# SCH_3S_10A_BMS_2022-07-15.net
KiCad netlist of a schematic drawn in EasyEDA
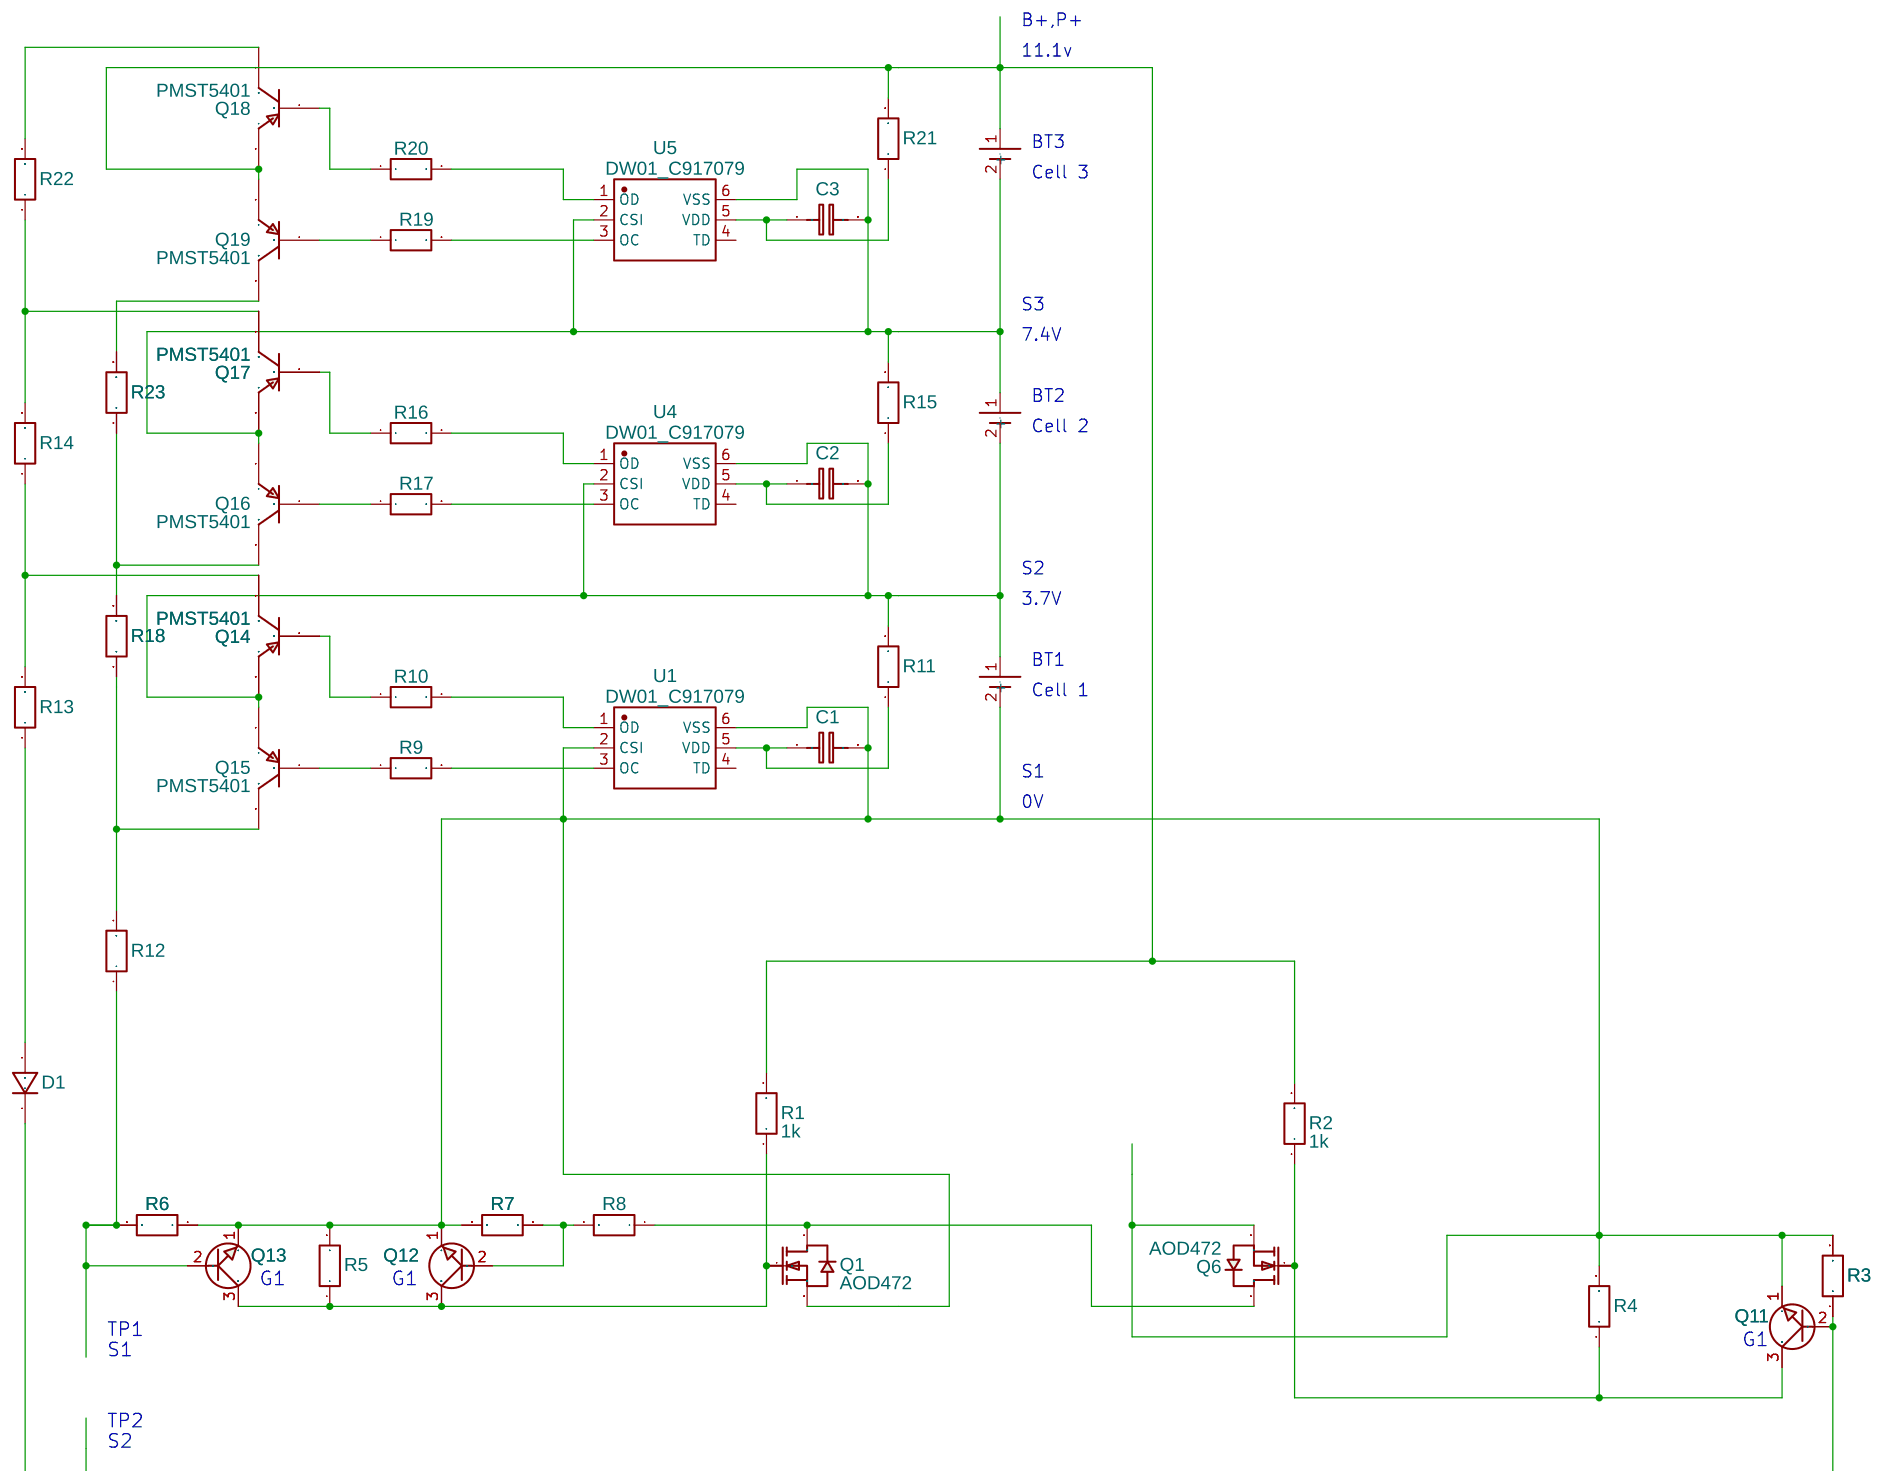
[diagram p0: 3s 10A Schematic]
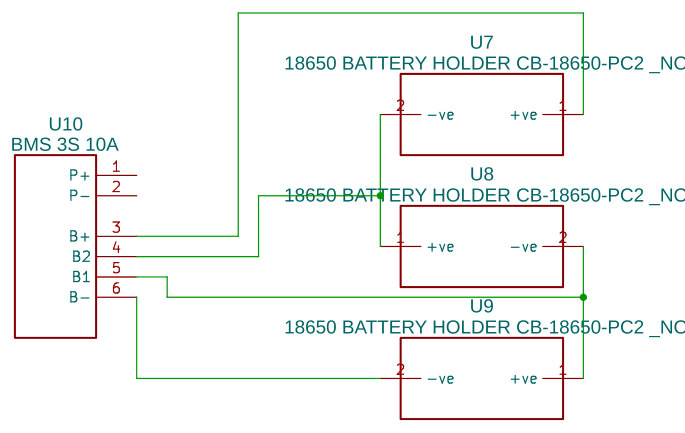
[diagram p1: 12v connection]

(export (version "E")
  (design (tool "Eeschema 10.0.6"))
  (components
    (comp (ref "C1") (value "0.1u") (libsource (lib "") (part "C_0603_EU")))
    (comp (ref "C2") (value "0.1u") (libsource (lib "") (part "C_0603_EU")))
    (comp (ref "C3") (value "0.1u") (libsource (lib "") (part "C_0603_EU")))
    (comp (ref "D1")
      (value "1N4007W")
      (fields (field (name "BOM_Supplier Part") "C328592"))
      (libsource (lib "") (part "1N4007W"))
    )
    (comp (ref "Q1")
      (value "AOD472")
      (fields (field (name "BOM_Supplier Part") "C693172"))
      (libsource (lib "") (part "AOD472"))
    )
    (comp (ref "Q6")
      (value "AOD472")
      (fields (field (name "BOM_Supplier Part") "C693172"))
      (libsource (lib "") (part "AOD472_1"))
    )
    (comp (ref "Q11") (value "2N2222") (libsource (lib "") (part "2N2222_1")))
    (comp (ref "Q12") (value "2N2222") (libsource (lib "") (part "2N2222_1")))
    (comp (ref "Q13") (value "2N2222") (libsource (lib "") (part "2N2222")))
    (comp (ref "Q14") (value "PMST5401") (libsource (lib "") (part "PMST5401")))
    (comp (ref "Q15") (value "PMST5401") (libsource (lib "") (part "PMST5401_1")))
    (comp (ref "Q16") (value "PMST5401") (libsource (lib "") (part "PMST5401_1")))
    (comp (ref "Q17") (value "PMST5401") (libsource (lib "") (part "PMST5401")))
    (comp (ref "Q18") (value "PMST5401") (libsource (lib "") (part "PMST5401")))
    (comp (ref "Q19") (value "PMST5401") (libsource (lib "") (part "PMST5401_1")))
    (comp (ref "R1") (value "1k") (libsource (lib "") (part "R_0603_EU")))
    (comp (ref "R2") (value "1k") (libsource (lib "") (part "R_0603_EU")))
    (comp (ref "R3") (value "1k") (libsource (lib "") (part "R_0603_EU")))
    (comp (ref "R4") (value "1k") (libsource (lib "") (part "R_0603_EU")))
    (comp (ref "R5") (value "1k") (libsource (lib "") (part "R_0603_EU")))
    (comp (ref "R6") (value "1k") (libsource (lib "") (part "R_0603_EU_2")))
    (comp (ref "R7") (value "1k") (libsource (lib "") (part "R_0603_EU_2")))
    (comp (ref "R8") (value "1k") (libsource (lib "") (part "R_0603_EU_2")))
    (comp (ref "R9") (value "1k") (libsource (lib "") (part "R_0603_EU_1")))
    (comp (ref "R10") (value "1k") (libsource (lib "") (part "R_0603_EU_1")))
    (comp (ref "R11") (value "1k") (libsource (lib "") (part "R_0603_EU")))
    (comp (ref "R12") (value "1k") (libsource (lib "") (part "R_0603_EU")))
    (comp (ref "R13") (value "1k") (libsource (lib "") (part "R_0603_EU")))
    (comp (ref "R14") (value "1k") (libsource (lib "") (part "R_0603_EU")))
    (comp (ref "R15") (value "1k") (libsource (lib "") (part "R_0603_EU")))
    (comp (ref "R16") (value "1k") (libsource (lib "") (part "R_0603_EU_1")))
    (comp (ref "R17") (value "1k") (libsource (lib "") (part "R_0603_EU_1")))
    (comp (ref "R18") (value "1k") (libsource (lib "") (part "R_0603_EU")))
    (comp (ref "R19") (value "1k") (libsource (lib "") (part "R_0603_EU_1")))
    (comp (ref "R20") (value "1k") (libsource (lib "") (part "R_0603_EU_1")))
    (comp (ref "R21") (value "1k") (libsource (lib "") (part "R_0603_EU")))
    (comp (ref "R22") (value "1k") (libsource (lib "") (part "R_0603_EU")))
    (comp (ref "R23") (value "1k") (libsource (lib "") (part "R_0603_EU")))
    (comp (ref "U1")
      (value "DW01_C917079")
      (fields (field (name "BOM_Manufacturer Part") "DW01") (field (name "BOM_Supplier Part") "C917079"))
      (libsource (lib "") (part "DW01_C917079"))
    )
    (comp (ref "U2") (value "Li-ion battery") (libsource (lib "") (part "Li-ion battery")))
    (comp (ref "U3") (value "Li-ion battery") (libsource (lib "") (part "Li-ion battery")))
    (comp (ref "U4")
      (value "DW01_C917079")
      (fields (field (name "BOM_Manufacturer Part") "DW01") (field (name "BOM_Supplier Part") "C917079"))
      (libsource (lib "") (part "DW01_C917079"))
    )
    (comp (ref "U5")
      (value "DW01_C917079")
      (fields (field (name "BOM_Manufacturer Part") "DW01") (field (name "BOM_Supplier Part") "C917079"))
      (libsource (lib "") (part "DW01_C917079"))
    )
    (comp (ref "U6") (value "Li-ion battery") (libsource (lib "") (part "Li-ion battery")))
    (comp (ref "U7")
      (value "18650 BATTERY HOLDER CB-18650-PC2 _NOTEMP COPY")
      (libsource (lib "") (part "18650 BATTERY HOLDER CB-18650-PC2 _NOTEMP COPY"))
    )
    (comp (ref "U8")
      (value "18650 BATTERY HOLDER CB-18650-PC2 _NOTEMP COPY")
      (libsource (lib "") (part "18650 BATTERY HOLDER CB-18650-PC2 _NOTEMP COPY_1"))
    )
    (comp (ref "U9")
      (value "18650 BATTERY HOLDER CB-18650-PC2 _NOTEMP COPY")
      (libsource (lib "") (part "18650 BATTERY HOLDER CB-18650-PC2 _NOTEMP COPY"))
    )
    (comp (ref "U10") (value "BMS 3S 10A") (libsource (lib "") (part "BMS 3S 10A")))
  )
  (nets
    (net (code "1") (name "Net-(D1-Pad2)") (class "Default")
      (node (ref "D1") (pin "2") (pinfunction "2_2") (pintype "unspecified"))
      (node (ref "R13") (pin "1") (pinfunction "1_1") (pintype "unspecified"))
    )
    (net (code "2") (name "Net-(Q1-D)") (class "Default")
      (node (ref "Q1") (pin "2") (pinfunction "D_2") (pintype "unspecified"))
      (node (ref "Q6") (pin "2") (pinfunction "D_2") (pintype "unspecified"))
      (node (ref "R8") (pin "1") (pinfunction "1_1") (pintype "unspecified"))
    )
    (net (code "3") (name "Net-(Q1-G)") (class "Default")
      (node (ref "Q1") (pin "1") (pinfunction "G_1") (pintype "unspecified"))
      (node (ref "Q12") (pin "3") (pinfunction "C_3") (pintype "unspecified"))
      (node (ref "Q13") (pin "3") (pinfunction "C_3") (pintype "unspecified"))
      (node (ref "R1") (pin "1") (pinfunction "1_1") (pintype "unspecified"))
      (node (ref "R5") (pin "1") (pinfunction "1_1") (pintype "unspecified"))
    )
    (net (code "4") (name "Net-(Q1-S)") (class "Default")
      (node (ref "C1") (pin "2") (pinfunction "2_2") (pintype "unspecified"))
      (node (ref "Q1") (pin "3") (pinfunction "S_3") (pintype "unspecified"))
      (node (ref "Q11") (pin "1") (pinfunction "E_1") (pintype "unspecified"))
      (node (ref "Q12") (pin "1") (pinfunction "E_1") (pintype "unspecified"))
      (node (ref "Q13") (pin "1") (pinfunction "E_1") (pintype "unspecified"))
      (node (ref "Q6") (pin "3") (pinfunction "S_3") (pintype "unspecified"))
      (node (ref "R3") (pin "2") (pinfunction "2_2") (pintype "unspecified"))
      (node (ref "R4") (pin "2") (pinfunction "2_2") (pintype "unspecified"))
      (node (ref "R5") (pin "2") (pinfunction "2_2") (pintype "unspecified"))
      (node (ref "R6") (pin "1") (pinfunction "1_1") (pintype "unspecified"))
      (node (ref "R7") (pin "2") (pinfunction "2_2") (pintype "unspecified"))
      (node (ref "U1") (pin "2") (pinfunction "CSI_2") (pintype "unspecified"))
      (node (ref "U1") (pin "6") (pinfunction "VSS_6") (pintype "unspecified"))
      (node (ref "U2") (pin "2") (pinfunction "-_2") (pintype "unspecified"))
    )
    (net (code "5") (name "Net-(Q11-B)") (class "Default")
      (node (ref "D1") (pin "1") (pinfunction "1_1") (pintype "unspecified"))
      (node (ref "Q11") (pin "2") (pinfunction "B_2") (pintype "input"))
      (node (ref "R3") (pin "1") (pinfunction "1_1") (pintype "unspecified"))
    )
    (net (code "6") (name "Net-(Q11-C)") (class "Default")
      (node (ref "Q11") (pin "3") (pinfunction "C_3") (pintype "unspecified"))
      (node (ref "Q6") (pin "1") (pinfunction "G_1") (pintype "unspecified"))
      (node (ref "R2") (pin "1") (pinfunction "1_1") (pintype "unspecified"))
      (node (ref "R4") (pin "1") (pinfunction "1_1") (pintype "unspecified"))
    )
    (net (code "7") (name "Net-(Q12-B)") (class "Default")
      (node (ref "Q12") (pin "2") (pinfunction "B_2") (pintype "input"))
      (node (ref "R7") (pin "1") (pinfunction "1_1") (pintype "unspecified"))
      (node (ref "R8") (pin "2") (pinfunction "2_2") (pintype "unspecified"))
    )
    (net (code "8") (name "Net-(Q13-B)") (class "Default")
      (node (ref "Q13") (pin "2") (pinfunction "B_2") (pintype "input"))
      (node (ref "R12") (pin "1") (pinfunction "1_1") (pintype "unspecified"))
      (node (ref "R6") (pin "2") (pinfunction "2_2") (pintype "unspecified"))
    )
    (net (code "9") (name "Net-(Q14-B)") (class "Default")
      (node (ref "Q14") (pin "1") (pinfunction "B_1") (pintype "unspecified"))
      (node (ref "R10") (pin "1") (pinfunction "1_1") (pintype "unspecified"))
    )
    (net (code "10") (name "Net-(Q14-C)") (class "Default")
      (node (ref "Q14") (pin "3") (pinfunction "C_3") (pintype "unspecified"))
      (node (ref "R13") (pin "2") (pinfunction "2_2") (pintype "unspecified"))
      (node (ref "R14") (pin "1") (pinfunction "1_1") (pintype "unspecified"))
    )
    (net (code "11") (name "Net-(Q14-E)") (class "Default")
      (node (ref "C2") (pin "2") (pinfunction "2_2") (pintype "unspecified"))
      (node (ref "Q14") (pin "2") (pinfunction "E_2") (pintype "unspecified"))
      (node (ref "Q15") (pin "2") (pinfunction "E_2") (pintype "unspecified"))
      (node (ref "R11") (pin "2") (pinfunction "2_2") (pintype "unspecified"))
      (node (ref "U2") (pin "1") (pinfunction "+_1") (pintype "unspecified"))
      (node (ref "U3") (pin "2") (pinfunction "-_2") (pintype "unspecified"))
      (node (ref "U4") (pin "2") (pinfunction "CSI_2") (pintype "unspecified"))
      (node (ref "U4") (pin "6") (pinfunction "VSS_6") (pintype "unspecified"))
    )
    (net (code "12") (name "Net-(Q15-B)") (class "Default")
      (node (ref "Q15") (pin "1") (pinfunction "B_1") (pintype "unspecified"))
      (node (ref "R9") (pin "1") (pinfunction "1_1") (pintype "unspecified"))
    )
    (net (code "13") (name "Net-(Q15-C)") (class "Default")
      (node (ref "Q15") (pin "3") (pinfunction "C_3") (pintype "unspecified"))
      (node (ref "R12") (pin "2") (pinfunction "2_2") (pintype "unspecified"))
      (node (ref "R18") (pin "1") (pinfunction "1_1") (pintype "unspecified"))
    )
    (net (code "14") (name "Net-(Q16-B)") (class "Default")
      (node (ref "Q16") (pin "1") (pinfunction "B_1") (pintype "unspecified"))
      (node (ref "R17") (pin "1") (pinfunction "1_1") (pintype "unspecified"))
    )
    (net (code "15") (name "Net-(Q16-C)") (class "Default")
      (node (ref "Q16") (pin "3") (pinfunction "C_3") (pintype "unspecified"))
      (node (ref "R18") (pin "2") (pinfunction "2_2") (pintype "unspecified"))
      (node (ref "R23") (pin "1") (pinfunction "1_1") (pintype "unspecified"))
    )
    (net (code "16") (name "Net-(Q16-E)") (class "Default")
      (node (ref "C3") (pin "2") (pinfunction "2_2") (pintype "unspecified"))
      (node (ref "Q16") (pin "2") (pinfunction "E_2") (pintype "unspecified"))
      (node (ref "Q17") (pin "2") (pinfunction "E_2") (pintype "unspecified"))
      (node (ref "R15") (pin "2") (pinfunction "2_2") (pintype "unspecified"))
      (node (ref "U3") (pin "1") (pinfunction "+_1") (pintype "unspecified"))
      (node (ref "U5") (pin "2") (pinfunction "CSI_2") (pintype "unspecified"))
      (node (ref "U5") (pin "6") (pinfunction "VSS_6") (pintype "unspecified"))
      (node (ref "U6") (pin "2") (pinfunction "-_2") (pintype "unspecified"))
    )
    (net (code "17") (name "Net-(Q17-B)") (class "Default")
      (node (ref "Q17") (pin "1") (pinfunction "B_1") (pintype "unspecified"))
      (node (ref "R16") (pin "1") (pinfunction "1_1") (pintype "unspecified"))
    )
    (net (code "18") (name "Net-(Q17-C)") (class "Default")
      (node (ref "Q17") (pin "3") (pinfunction "C_3") (pintype "unspecified"))
      (node (ref "R14") (pin "2") (pinfunction "2_2") (pintype "unspecified"))
      (node (ref "R22") (pin "1") (pinfunction "1_1") (pintype "unspecified"))
    )
    (net (code "19") (name "Net-(Q18-B)") (class "Default")
      (node (ref "Q18") (pin "1") (pinfunction "B_1") (pintype "unspecified"))
      (node (ref "R20") (pin "1") (pinfunction "1_1") (pintype "unspecified"))
    )
    (net (code "20") (name "Net-(Q18-C)") (class "Default")
      (node (ref "Q18") (pin "3") (pinfunction "C_3") (pintype "unspecified"))
      (node (ref "R22") (pin "2") (pinfunction "2_2") (pintype "unspecified"))
    )
    (net (code "21") (name "Net-(Q18-E)") (class "Default")
      (node (ref "Q18") (pin "2") (pinfunction "E_2") (pintype "unspecified"))
      (node (ref "Q19") (pin "2") (pinfunction "E_2") (pintype "unspecified"))
      (node (ref "R1") (pin "2") (pinfunction "2_2") (pintype "unspecified"))
      (node (ref "R2") (pin "2") (pinfunction "2_2") (pintype "unspecified"))
      (node (ref "R21") (pin "2") (pinfunction "2_2") (pintype "unspecified"))
      (node (ref "U6") (pin "1") (pinfunction "+_1") (pintype "unspecified"))
    )
    (net (code "22") (name "Net-(Q19-B)") (class "Default")
      (node (ref "Q19") (pin "1") (pinfunction "B_1") (pintype "unspecified"))
      (node (ref "R19") (pin "1") (pinfunction "1_1") (pintype "unspecified"))
    )
    (net (code "23") (name "Net-(Q19-C)") (class "Default")
      (node (ref "Q19") (pin "3") (pinfunction "C_3") (pintype "unspecified"))
      (node (ref "R23") (pin "2") (pinfunction "2_2") (pintype "unspecified"))
    )
    (net (code "24") (name "Net-(U1-OC)") (class "Default")
      (node (ref "R9") (pin "2") (pinfunction "2_2") (pintype "unspecified"))
      (node (ref "U1") (pin "3") (pinfunction "OC_3") (pintype "unspecified"))
    )
    (net (code "25") (name "Net-(U1-OD)") (class "Default")
      (node (ref "R10") (pin "2") (pinfunction "2_2") (pintype "unspecified"))
      (node (ref "U1") (pin "1") (pinfunction "OD_1") (pintype "unspecified"))
    )
    (net (code "26") (name "Net-(U1-VDD)") (class "Default")
      (node (ref "C1") (pin "1") (pinfunction "1_1") (pintype "unspecified"))
      (node (ref "R11") (pin "1") (pinfunction "1_1") (pintype "unspecified"))
      (node (ref "U1") (pin "5") (pinfunction "VDD_5") (pintype "unspecified"))
    )
    (net (code "27") (name "Net-(U4-OC)") (class "Default")
      (node (ref "R17") (pin "2") (pinfunction "2_2") (pintype "unspecified"))
      (node (ref "U4") (pin "3") (pinfunction "OC_3") (pintype "unspecified"))
    )
    (net (code "28") (name "Net-(U4-OD)") (class "Default")
      (node (ref "R16") (pin "2") (pinfunction "2_2") (pintype "unspecified"))
      (node (ref "U4") (pin "1") (pinfunction "OD_1") (pintype "unspecified"))
    )
    (net (code "29") (name "Net-(U4-VDD)") (class "Default")
      (node (ref "C2") (pin "1") (pinfunction "1_1") (pintype "unspecified"))
      (node (ref "R15") (pin "1") (pinfunction "1_1") (pintype "unspecified"))
      (node (ref "U4") (pin "5") (pinfunction "VDD_5") (pintype "unspecified"))
    )
    (net (code "30") (name "Net-(U5-OC)") (class "Default")
      (node (ref "R19") (pin "2") (pinfunction "2_2") (pintype "unspecified"))
      (node (ref "U5") (pin "3") (pinfunction "OC_3") (pintype "unspecified"))
    )
    (net (code "31") (name "Net-(U5-OD)") (class "Default")
      (node (ref "R20") (pin "2") (pinfunction "2_2") (pintype "unspecified"))
      (node (ref "U5") (pin "1") (pinfunction "OD_1") (pintype "unspecified"))
    )
    (net (code "32") (name "Net-(U5-VDD)") (class "Default")
      (node (ref "C3") (pin "1") (pinfunction "1_1") (pintype "unspecified"))
      (node (ref "R21") (pin "1") (pinfunction "1_1") (pintype "unspecified"))
      (node (ref "U5") (pin "5") (pinfunction "VDD_5") (pintype "unspecified"))
    )
    (net (code "33") (name "Net-(U10-B+)") (class "Default")
      (node (ref "U10") (pin "3") (pinfunction "B+_3") (pintype "unspecified"))
      (node (ref "U7") (pin "1") (pinfunction "+ve_1") (pintype "passive"))
    )
    (net (code "34") (name "Net-(U10-B-)") (class "Default")
      (node (ref "U10") (pin "6") (pinfunction "B-_6") (pintype "unspecified"))
      (node (ref "U9") (pin "2") (pinfunction "-ve_2") (pintype "passive"))
    )
    (net (code "35") (name "Net-(U10-B1)") (class "Default")
      (node (ref "U10") (pin "5") (pinfunction "B1_5") (pintype "unspecified"))
      (node (ref "U8") (pin "2") (pinfunction "-ve_2") (pintype "passive"))
      (node (ref "U9") (pin "1") (pinfunction "+ve_1") (pintype "passive"))
    )
    (net (code "36") (name "Net-(U10-B2)") (class "Default")
      (node (ref "U10") (pin "4") (pinfunction "B2_4") (pintype "unspecified"))
      (node (ref "U7") (pin "2") (pinfunction "-ve_2") (pintype "passive"))
      (node (ref "U8") (pin "1") (pinfunction "+ve_1") (pintype "passive"))
    )
    (net (code "37") (name "unconnected-(U1-TD-Pad4)") (class "Default")
      (node (ref "U1") (pin "4") (pinfunction "TD_4") (pintype "unspecified"))
    )
    (net (code "38") (name "unconnected-(U4-TD-Pad4)") (class "Default")
      (node (ref "U4") (pin "4") (pinfunction "TD_4") (pintype "unspecified"))
    )
    (net (code "39") (name "unconnected-(U5-TD-Pad4)") (class "Default")
      (node (ref "U5") (pin "4") (pinfunction "TD_4") (pintype "unspecified"))
    )
    (net (code "40") (name "unconnected-(U10-P+-Pad1)") (class "Default")
      (node (ref "U10") (pin "1") (pinfunction "P+_1") (pintype "unspecified"))
    )
    (net (code "41") (name "unconnected-(U10-P--Pad2)") (class "Default")
      (node (ref "U10") (pin "2") (pinfunction "P-_2") (pintype "unspecified"))
    )
  )
)
